# ESP32S3.net
KiCad netlist of a schematic drawn in Altium Designer
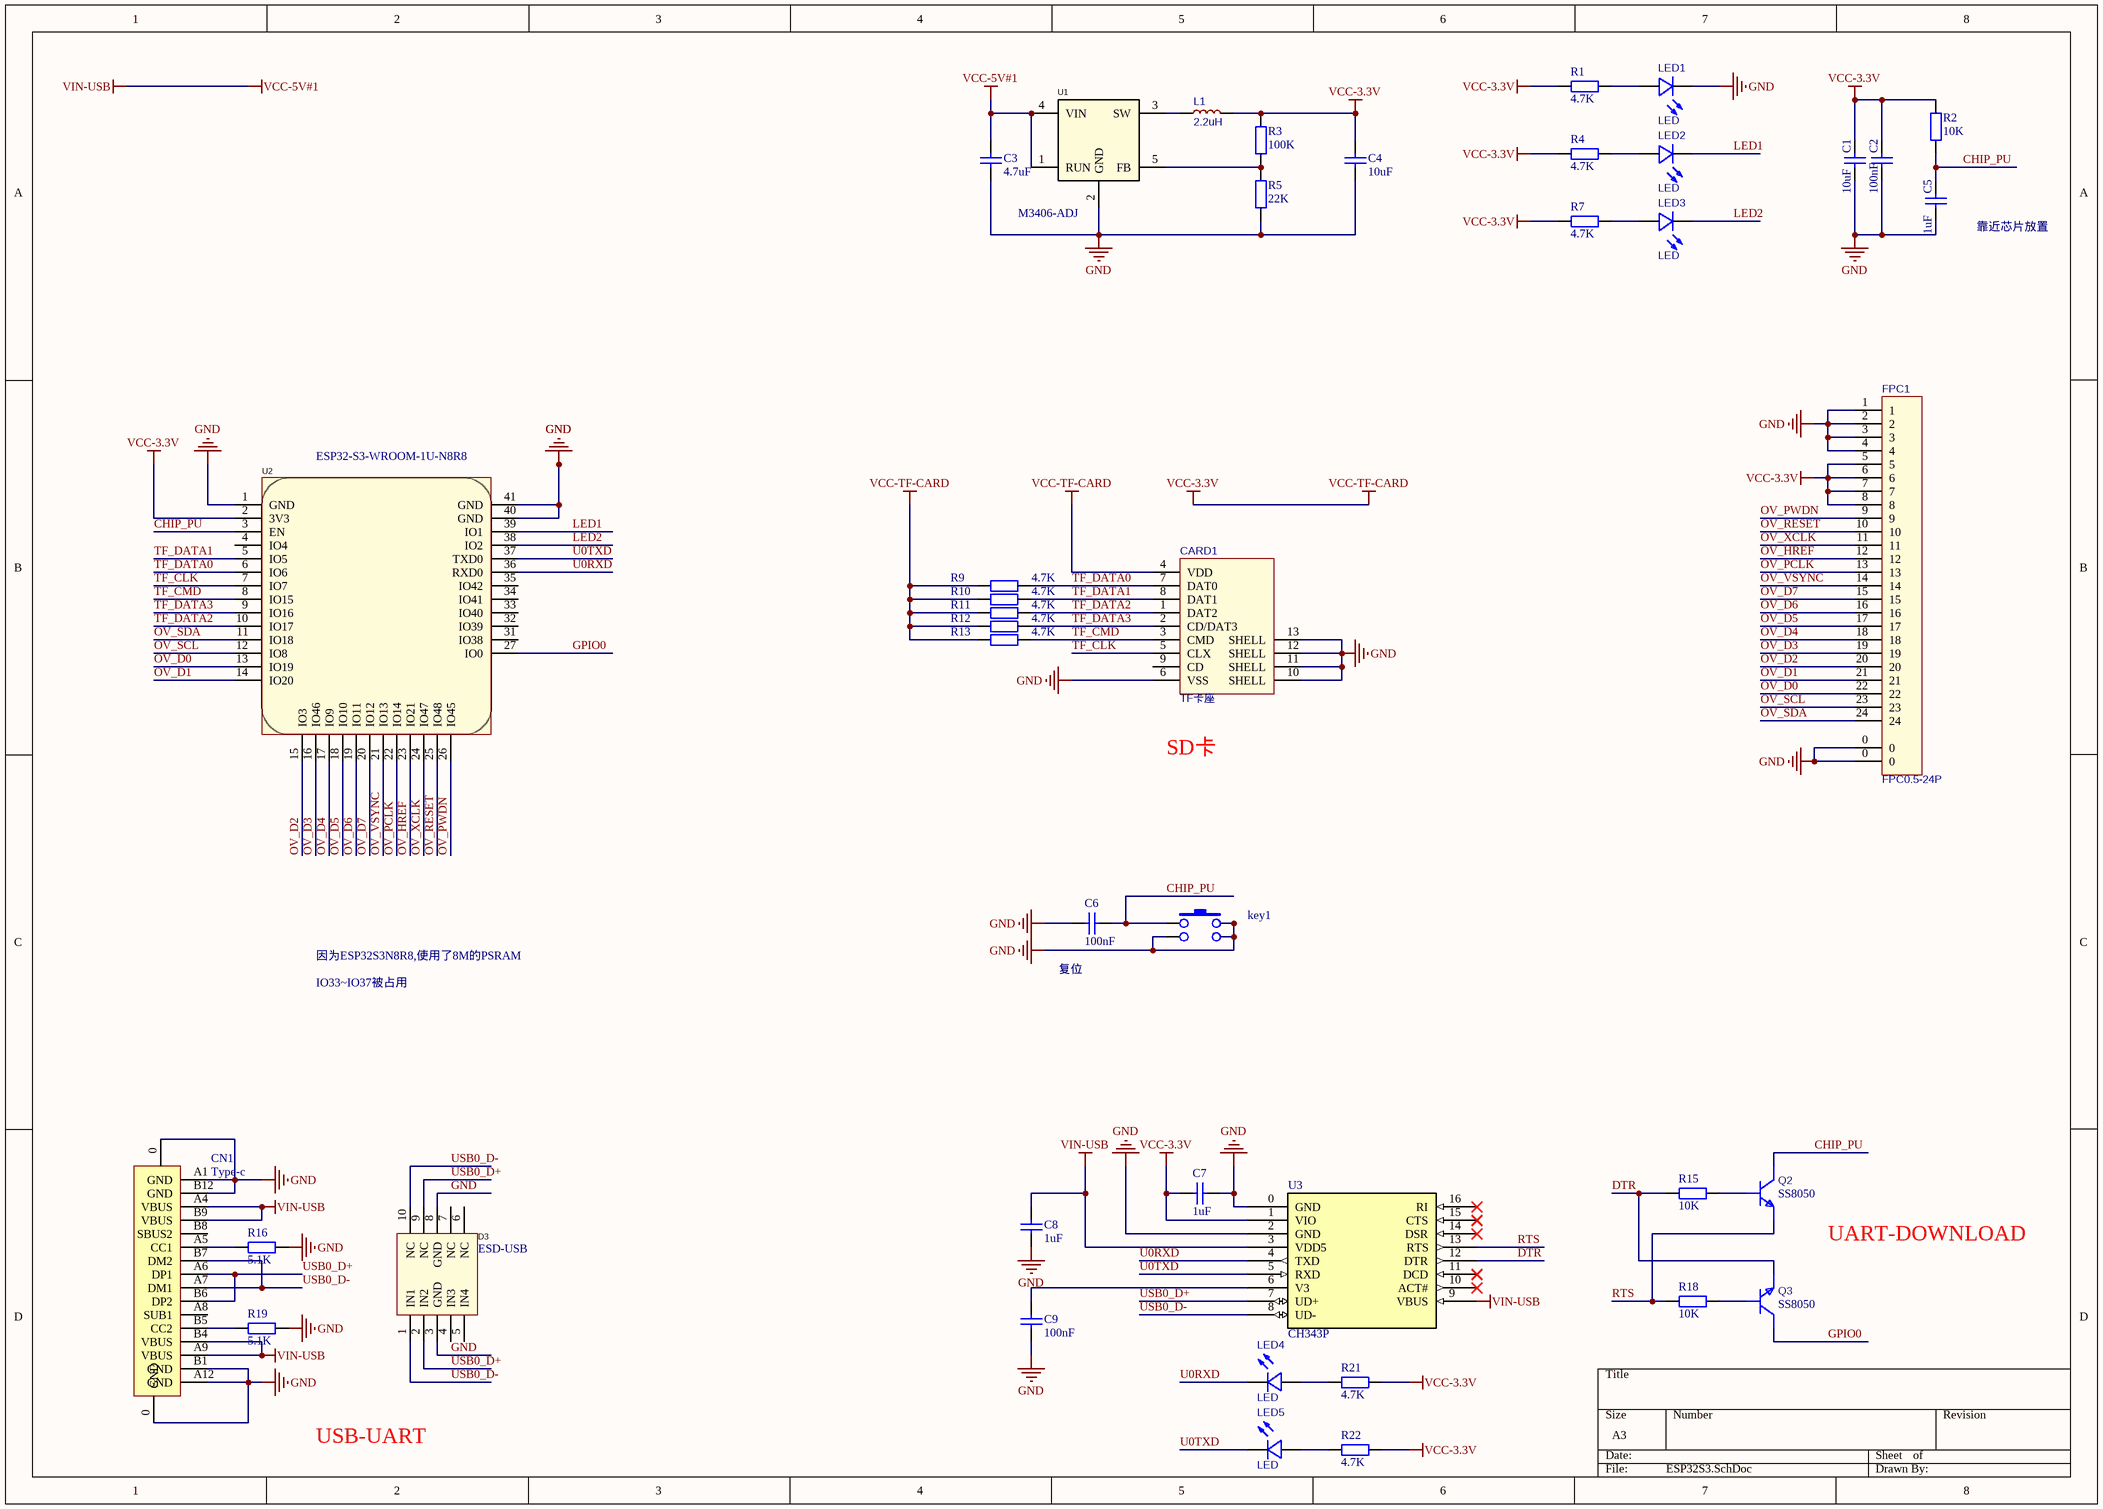
[diagram p0: ESP32S3.SchDoc]

(export (version "E")
  (design (tool "Eeschema 10.0.6"))
  (components
    (comp (ref "C1")
      (value "10uF")
      (footprint "0603-C")
      (description "贴片电容")
      (libsource (lib "封装库") (part "C"))
    )
    (comp (ref "C2")
      (value "100nF")
      (footprint "0603-C")
      (description "贴片电容")
      (libsource (lib "封装库") (part "C"))
    )
    (comp (ref "C3")
      (value "4.7uF")
      (footprint "0603-C")
      (description "贴片电容")
      (libsource (lib "封装库") (part "C"))
    )
    (comp (ref "C4")
      (value "10uF")
      (footprint "0603-C")
      (description "贴片电容")
      (libsource (lib "封装库") (part "C"))
    )
    (comp (ref "C5")
      (value "1uF")
      (footprint "0603-C")
      (description "贴片电容")
      (libsource (lib "封装库") (part "C"))
    )
    (comp (ref "C6")
      (value "100nF")
      (footprint "0603-C")
      (description "贴片电容")
      (libsource (lib "封装库") (part "C"))
    )
    (comp (ref "C7")
      (value "1uF")
      (footprint "0603-C")
      (description "贴片电容")
      (libsource (lib "封装库") (part "C"))
    )
    (comp (ref "C8")
      (value "1uF")
      (footprint "0603-C")
      (description "贴片电容")
      (libsource (lib "封装库") (part "C"))
    )
    (comp (ref "C9")
      (value "100nF")
      (footprint "0603-C")
      (description "贴片电容")
      (libsource (lib "封装库") (part "C"))
    )
    (comp (ref "CARD1")
      (value "TF卡座")
      (footprint "TF")
      (fields
        (field (name "BOM_SUPPLIER PART") "C283232")
        (field (name "BOM_MANUFACTURER PART") "THD2528-11SD-GF")
        (field (name "CONTRIBUTOR") "LCSC")
      )
      (libsource (lib "封装库") (part "TF卡座"))
    )
    (comp (ref "CN1")
      (value "Type-c")
      (footprint "Type-c 16pin")
      (description "U262-161N-4BVC11")
      (libsource (lib "封装") (part "Type-c"))
    )
    (comp (ref "D3")
      (value "ESD-USB")
      (footprint "SLP2510P8")
      (description "RClamp0524PATCT")
      (fields (field (name "MANUFACTURER") "SEMTECH"))
      (libsource (lib "封装库") (part "ESD-USB"))
    )
    (comp (ref "FPC1")
      (value "FPC0.5-24P")
      (footprint "FPC-SMD_P0.50-24P_XJ-FGS")
      (fields (field (name "BOM_SUPPLIER PART") "C132514") (field (name "CONTRIBUTOR") "LCSC"))
      (libsource (lib "封装库") (part "FPC0.5-24P"))
    )
    (comp (ref "key1") (value "KEY") (footprint "轻触开关侧按3*6*3.5") (libsource (lib "封装库") (part "轻触开关3*6*3.6")))
    (comp (ref "L1")
      (value "2.2uH")
      (footprint "电感 4.2X4.4")
      (description "L")
      (fields
        (field (name "BOM_MANUFACTURER PART") "UPZ2012D800-4R0TF")
        (field (name "BOM_SUPPLIER PART") "C145060")
        (field (name "CONTRIBUTOR") "LCSC")
      )
      (libsource (lib "封装库") (part "L"))
    )
    (comp (ref "LED1")
      (value "LED")
      (footprint "LED-0603")
      (fields
        (field (name "BOM_SUPPLIER PART") "C118334")
        (field (name "BOM_MANUFACTURER PART") "D-G060306G1-KS2")
        (field (name "CONTRIBUTOR") "LCSC")
      )
      (libsource (lib "封装库") (part "LED"))
    )
    (comp (ref "LED2")
      (value "LED")
      (footprint "LED-0603")
      (fields
        (field (name "BOM_SUPPLIER PART") "C118334")
        (field (name "BOM_MANUFACTURER PART") "D-G060306G1-KS2")
        (field (name "CONTRIBUTOR") "LCSC")
      )
      (libsource (lib "封装库") (part "LED"))
    )
    (comp (ref "LED3")
      (value "LED")
      (footprint "LED-0603")
      (fields
        (field (name "BOM_SUPPLIER PART") "C118334")
        (field (name "BOM_MANUFACTURER PART") "D-G060306G1-KS2")
        (field (name "CONTRIBUTOR") "LCSC")
      )
      (libsource (lib "封装库") (part "LED"))
    )
    (comp (ref "LED4")
      (value "LED")
      (footprint "LED-0603")
      (fields
        (field (name "BOM_SUPPLIER PART") "C118334")
        (field (name "BOM_MANUFACTURER PART") "D-G060306G1-KS2")
        (field (name "CONTRIBUTOR") "LCSC")
      )
      (libsource (lib "封装库") (part "LED"))
    )
    (comp (ref "LED5")
      (value "LED")
      (footprint "LED-0603")
      (fields
        (field (name "BOM_SUPPLIER PART") "C118334")
        (field (name "BOM_MANUFACTURER PART") "D-G060306G1-KS2")
        (field (name "CONTRIBUTOR") "LCSC")
      )
      (libsource (lib "封装库") (part "LED"))
    )
    (comp (ref "Q2") (value "SS8050") (footprint "SOT23-3M") (libsource (lib "封装库") (part "SS8050")))
    (comp (ref "Q3") (value "SS8050") (footprint "SOT23-3M") (libsource (lib "封装库") (part "SS8050")))
    (comp (ref "R1")
      (value "4.7K")
      (footprint "0603-R")
      (description "贴片电阻")
      (libsource (lib "封装库") (part "R"))
    )
    (comp (ref "R2")
      (value "10K")
      (footprint "0603-R")
      (description "贴片电阻")
      (libsource (lib "封装库") (part "R"))
    )
    (comp (ref "R3")
      (value "100K")
      (footprint "0603-R")
      (description "贴片电阻")
      (libsource (lib "封装库") (part "R"))
    )
    (comp (ref "R4")
      (value "4.7K")
      (footprint "0603-R")
      (description "贴片电阻")
      (libsource (lib "封装库") (part "R"))
    )
    (comp (ref "R5")
      (value "22K")
      (footprint "0603-R")
      (description "贴片电阻")
      (libsource (lib "封装库") (part "R"))
    )
    (comp (ref "R7")
      (value "4.7K")
      (footprint "0603-R")
      (description "贴片电阻")
      (libsource (lib "封装库") (part "R"))
    )
    (comp (ref "R9")
      (value "4.7K")
      (footprint "0603-R")
      (description "贴片电阻")
      (libsource (lib "封装库") (part "R"))
    )
    (comp (ref "R10")
      (value "4.7K")
      (footprint "0603-R")
      (description "贴片电阻")
      (libsource (lib "封装库") (part "R"))
    )
    (comp (ref "R11")
      (value "4.7K")
      (footprint "0603-R")
      (description "贴片电阻")
      (libsource (lib "封装库") (part "R"))
    )
    (comp (ref "R12")
      (value "4.7K")
      (footprint "0603-R")
      (description "贴片电阻")
      (libsource (lib "封装库") (part "R"))
    )
    (comp (ref "R13")
      (value "4.7K")
      (footprint "0603-R")
      (description "贴片电阻")
      (libsource (lib "封装库") (part "R"))
    )
    (comp (ref "R15")
      (value "10K")
      (footprint "0603-R")
      (description "贴片电阻")
      (libsource (lib "封装库") (part "R"))
    )
    (comp (ref "R16")
      (value "5.1K")
      (footprint "0603-R")
      (description "贴片电阻")
      (libsource (lib "封装库") (part "R"))
    )
    (comp (ref "R18")
      (value "10K")
      (footprint "0603-R")
      (description "贴片电阻")
      (libsource (lib "封装库") (part "R"))
    )
    (comp (ref "R19")
      (value "5.1K")
      (footprint "0603-R")
      (description "贴片电阻")
      (libsource (lib "封装库") (part "R"))
    )
    (comp (ref "R21")
      (value "4.7K")
      (footprint "0603-R")
      (description "贴片电阻")
      (libsource (lib "封装库") (part "R"))
    )
    (comp (ref "R22")
      (value "4.7K")
      (footprint "0603-R")
      (description "贴片电阻")
      (libsource (lib "封装库") (part "R"))
    )
    (comp (ref "U1")
      (value "M3406-ADJ")
      (footprint "M3406-ADJ")
      (fields (field (name "MANUFACTURER") "西安航天民芯"))
      (libsource (lib "封装库") (part "M3406-ADJ"))
    )
    (comp (ref "U2")
      (value "ESP32-S3-WROOM-1U-N8R8")
      (footprint "WIRELM-SMD_ESP32-S3-WROOM-1U")
      (fields
        (field (name "MANUFACTURER") "ESPRESSIF(乐鑫)")
        (field (name "MANUFACTURER PART") "ESP32-S3-WROOM-1U-N8")
      )
      (libsource (lib "封装库") (part "ESP32-S3-WROOM-1U-N8R8"))
    )
    (comp (ref "U3")
      (value "CH343P")
      (footprint "QFN16_3X3")
      (description "USB to high speed enhanced TTL Serial / UART")
      (libsource (lib "封装库") (part "CH343P"))
    )
  )
  (nets
    (net (code "1") (name "/CHIP_PU") (class "Default")
      (node (ref "C5") (pin "1") (pinfunction "1_1") (pintype "passive"))
      (node (ref "C6") (pin "1") (pinfunction "1_1") (pintype "passive"))
      (node (ref "Q2") (pin "3") (pinfunction "C_3") (pintype "passive"))
      (node (ref "R2") (pin "1") (pinfunction "1_1") (pintype "passive"))
      (node (ref "U2") (pin "3") (pinfunction "EN_3") (pintype "passive"))
      (node (ref "key1") (pin "1") (pinfunction "1_1") (pintype "passive"))
    )
    (net (code "2") (name "/DTR") (class "Default")
      (node (ref "Q3") (pin "2") (pinfunction "E_2") (pintype "passive"))
      (node (ref "R15") (pin "1") (pinfunction "1_1") (pintype "passive"))
      (node (ref "U3") (pin "12") (pinfunction "DTR_12") (pintype "output"))
    )
    (net (code "3") (name "/GPIO0") (class "Default")
      (node (ref "Q3") (pin "3") (pinfunction "C_3") (pintype "passive"))
      (node (ref "U2") (pin "27") (pinfunction "IO0_27") (pintype "passive"))
    )
    (net (code "4") (name "/LED1") (class "Default")
      (node (ref "LED2") (pin "1") (pinfunction "-_1") (pintype "passive"))
      (node (ref "U2") (pin "39") (pinfunction "IO1_39") (pintype "passive"))
    )
    (net (code "5") (name "/LED2") (class "Default")
      (node (ref "LED3") (pin "1") (pinfunction "-_1") (pintype "passive"))
      (node (ref "U2") (pin "38") (pinfunction "IO2_38") (pintype "passive"))
    )
    (net (code "6") (name "/OV_D0") (class "Default")
      (node (ref "FPC1") (pin "22") (pinfunction "22_22") (pintype "passive"))
      (node (ref "U2") (pin "13") (pinfunction "IO19_13") (pintype "passive"))
    )
    (net (code "7") (name "/OV_D1") (class "Default")
      (node (ref "FPC1") (pin "21") (pinfunction "21_21") (pintype "passive"))
      (node (ref "U2") (pin "14") (pinfunction "IO20_14") (pintype "passive"))
    )
    (net (code "8") (name "/OV_D2") (class "Default")
      (node (ref "FPC1") (pin "20") (pinfunction "20_20") (pintype "passive"))
      (node (ref "U2") (pin "15") (pinfunction "IO3_15") (pintype "passive"))
    )
    (net (code "9") (name "/OV_D3") (class "Default")
      (node (ref "FPC1") (pin "19") (pinfunction "19_19") (pintype "passive"))
      (node (ref "U2") (pin "16") (pinfunction "IO46_16") (pintype "passive"))
    )
    (net (code "10") (name "/OV_D4") (class "Default")
      (node (ref "FPC1") (pin "18") (pinfunction "18_18") (pintype "passive"))
      (node (ref "U2") (pin "17") (pinfunction "IO9_17") (pintype "passive"))
    )
    (net (code "11") (name "/OV_D5") (class "Default")
      (node (ref "FPC1") (pin "17") (pinfunction "17_17") (pintype "passive"))
      (node (ref "U2") (pin "18") (pinfunction "IO10_18") (pintype "passive"))
    )
    (net (code "12") (name "/OV_D6") (class "Default")
      (node (ref "FPC1") (pin "16") (pinfunction "16_16") (pintype "passive"))
      (node (ref "U2") (pin "19") (pinfunction "IO11_19") (pintype "passive"))
    )
    (net (code "13") (name "/OV_D7") (class "Default")
      (node (ref "FPC1") (pin "15") (pinfunction "15_15") (pintype "passive"))
      (node (ref "U2") (pin "20") (pinfunction "IO12_20") (pintype "passive"))
    )
    (net (code "14") (name "/OV_HREF") (class "Default")
      (node (ref "FPC1") (pin "12") (pinfunction "12_12") (pintype "passive"))
      (node (ref "U2") (pin "23") (pinfunction "IO21_23") (pintype "passive"))
    )
    (net (code "15") (name "/OV_PCLK") (class "Default")
      (node (ref "FPC1") (pin "13") (pinfunction "13_13") (pintype "passive"))
      (node (ref "U2") (pin "22") (pinfunction "IO14_22") (pintype "passive"))
    )
    (net (code "16") (name "/OV_PWDN") (class "Default")
      (node (ref "FPC1") (pin "9") (pinfunction "9_9") (pintype "passive"))
      (node (ref "U2") (pin "26") (pinfunction "IO45_26") (pintype "passive"))
    )
    (net (code "17") (name "/OV_RESET") (class "Default")
      (node (ref "FPC1") (pin "10") (pinfunction "10_10") (pintype "passive"))
      (node (ref "U2") (pin "25") (pinfunction "IO48_25") (pintype "passive"))
    )
    (net (code "18") (name "/OV_SCL") (class "Default")
      (node (ref "FPC1") (pin "23") (pinfunction "23_23") (pintype "passive"))
      (node (ref "U2") (pin "12") (pinfunction "IO8_12") (pintype "passive"))
    )
    (net (code "19") (name "/OV_SDA") (class "Default")
      (node (ref "FPC1") (pin "24") (pinfunction "24_24") (pintype "passive"))
      (node (ref "U2") (pin "11") (pinfunction "IO18_11") (pintype "passive"))
    )
    (net (code "20") (name "/OV_VSYNC") (class "Default")
      (node (ref "FPC1") (pin "14") (pinfunction "14_14") (pintype "passive"))
      (node (ref "U2") (pin "21") (pinfunction "IO13_21") (pintype "passive"))
    )
    (net (code "21") (name "/OV_XCLK") (class "Default")
      (node (ref "FPC1") (pin "11") (pinfunction "11_11") (pintype "passive"))
      (node (ref "U2") (pin "24") (pinfunction "IO47_24") (pintype "passive"))
    )
    (net (code "22") (name "/RTS") (class "Default")
      (node (ref "Q2") (pin "2") (pinfunction "E_2") (pintype "passive"))
      (node (ref "R18") (pin "1") (pinfunction "1_1") (pintype "passive"))
      (node (ref "U3") (pin "13") (pinfunction "RTS_13") (pintype "output"))
    )
    (net (code "23") (name "/TF_CLK") (class "Default")
      (node (ref "CARD1") (pin "5") (pinfunction "CLX_5") (pintype "passive"))
      (node (ref "U2") (pin "7") (pinfunction "IO7_7") (pintype "passive"))
    )
    (net (code "24") (name "/TF_CMD") (class "Default")
      (node (ref "CARD1") (pin "3") (pinfunction "CMD_3") (pintype "passive"))
      (node (ref "R13") (pin "2") (pinfunction "2_2") (pintype "passive"))
      (node (ref "U2") (pin "8") (pinfunction "IO15_8") (pintype "passive"))
    )
    (net (code "25") (name "/TF_DATA0") (class "Default")
      (node (ref "CARD1") (pin "7") (pinfunction "DAT0_7") (pintype "passive"))
      (node (ref "R9") (pin "2") (pinfunction "2_2") (pintype "passive"))
      (node (ref "U2") (pin "6") (pinfunction "IO6_6") (pintype "passive"))
    )
    (net (code "26") (name "/TF_DATA1") (class "Default")
      (node (ref "CARD1") (pin "8") (pinfunction "DAT1_8") (pintype "passive"))
      (node (ref "R10") (pin "2") (pinfunction "2_2") (pintype "passive"))
      (node (ref "U2") (pin "5") (pinfunction "IO5_5") (pintype "passive"))
    )
    (net (code "27") (name "/TF_DATA2") (class "Default")
      (node (ref "CARD1") (pin "1") (pinfunction "DAT2_1") (pintype "passive"))
      (node (ref "R11") (pin "2") (pinfunction "2_2") (pintype "passive"))
      (node (ref "U2") (pin "10") (pinfunction "IO17_10") (pintype "passive"))
    )
    (net (code "28") (name "/TF_DATA3") (class "Default")
      (node (ref "CARD1") (pin "2") (pinfunction "CD/DAT3_2") (pintype "passive"))
      (node (ref "R12") (pin "2") (pinfunction "2_2") (pintype "passive"))
      (node (ref "U2") (pin "9") (pinfunction "IO16_9") (pintype "passive"))
    )
    (net (code "29") (name "/U0RXD") (class "Default")
      (node (ref "LED4") (pin "1") (pinfunction "-_1") (pintype "passive"))
      (node (ref "U2") (pin "36") (pinfunction "RXD0_36") (pintype "passive"))
      (node (ref "U3") (pin "4") (pinfunction "TXD_4") (pintype "output"))
    )
    (net (code "30") (name "/U0TXD") (class "Default")
      (node (ref "LED5") (pin "1") (pinfunction "-_1") (pintype "passive"))
      (node (ref "U2") (pin "37") (pinfunction "TXD0_37") (pintype "passive"))
      (node (ref "U3") (pin "5") (pinfunction "RXD_5") (pintype "input"))
    )
    (net (code "31") (name "/USB0_D+") (class "Default")
      (node (ref "CN1") (pin "A6") (pinfunction "DP1_A6") (pintype "passive"))
      (node (ref "CN1") (pin "B6") (pinfunction "DP2_B6") (pintype "passive"))
      (node (ref "D3") (pin "2") (pinfunction "IN2_2") (pintype "passive"))
      (node (ref "D3") (pin "9") (pinfunction "NC_9") (pintype "passive"))
      (node (ref "U3") (pin "7") (pinfunction "UD+_7") (pintype "bidirectional"))
    )
    (net (code "32") (name "/USB0_D-") (class "Default")
      (node (ref "CN1") (pin "A7") (pinfunction "DM1_A7") (pintype "passive"))
      (node (ref "CN1") (pin "B7") (pinfunction "DM2_B7") (pintype "passive"))
      (node (ref "D3") (pin "1") (pinfunction "IN1_1") (pintype "passive"))
      (node (ref "D3") (pin "10") (pinfunction "NC_10") (pintype "passive"))
      (node (ref "U3") (pin "8") (pinfunction "UD-_8") (pintype "bidirectional"))
    )
    (net (code "33") (name "GND") (class "Default")
      (node (ref "C1") (pin "1") (pinfunction "1_1") (pintype "passive"))
      (node (ref "C2") (pin "2") (pinfunction "2_2") (pintype "passive"))
      (node (ref "C3") (pin "1") (pinfunction "1_1") (pintype "passive"))
      (node (ref "C4") (pin "1") (pinfunction "1_1") (pintype "passive"))
      (node (ref "C5") (pin "2") (pinfunction "2_2") (pintype "passive"))
      (node (ref "C6") (pin "2") (pinfunction "2_2") (pintype "passive"))
      (node (ref "C7") (pin "2") (pinfunction "2_2") (pintype "passive"))
      (node (ref "C8") (pin "2") (pinfunction "2_2") (pintype "passive"))
      (node (ref "C9") (pin "2") (pinfunction "2_2") (pintype "passive"))
      (node (ref "CARD1") (pin "10") (pinfunction "SHELL_10") (pintype "passive"))
      (node (ref "CARD1") (pin "11") (pinfunction "SHELL_11") (pintype "passive"))
      (node (ref "CARD1") (pin "12") (pinfunction "SHELL_12") (pintype "passive"))
      (node (ref "CARD1") (pin "13") (pinfunction "SHELL_13") (pintype "passive"))
      (node (ref "CARD1") (pin "6") (pinfunction "VSS_6") (pintype "passive"))
      (node (ref "CN1") (pin "0") (pinfunction "GND_0") (pintype "passive"))
      (node (ref "CN1") (pin "A1") (pinfunction "GND_A1") (pintype "passive"))
      (node (ref "CN1") (pin "A12") (pinfunction "GND_A12") (pintype "passive"))
      (node (ref "CN1") (pin "B1") (pinfunction "GND_B1") (pintype "passive"))
      (node (ref "CN1") (pin "B12") (pinfunction "GND_B12") (pintype "passive"))
      (node (ref "D3") (pin "3") (pinfunction "GND_3") (pintype "passive"))
      (node (ref "D3") (pin "8") (pinfunction "GND_8") (pintype "passive"))
      (node (ref "FPC1") (pin "0") (pinfunction "0_0") (pintype "passive"))
      (node (ref "FPC1") (pin "1") (pinfunction "1_1") (pintype "passive"))
      (node (ref "FPC1") (pin "2") (pinfunction "2_2") (pintype "passive"))
      (node (ref "FPC1") (pin "3") (pinfunction "3_3") (pintype "passive"))
      (node (ref "FPC1") (pin "4") (pinfunction "4_4") (pintype "passive"))
      (node (ref "LED1") (pin "1") (pinfunction "-_1") (pintype "passive"))
      (node (ref "R16") (pin "2") (pinfunction "2_2") (pintype "passive"))
      (node (ref "R19") (pin "2") (pinfunction "2_2") (pintype "passive"))
      (node (ref "R5") (pin "2") (pinfunction "2_2") (pintype "passive"))
      (node (ref "U1") (pin "2") (pinfunction "GND_2") (pintype "passive"))
      (node (ref "U2") (pin "1") (pinfunction "GND_1") (pintype "passive"))
      (node (ref "U2") (pin "40") (pinfunction "GND_40") (pintype "passive"))
      (node (ref "U2") (pin "41") (pinfunction "GND_41") (pintype "passive"))
      (node (ref "U3") (pin "0") (pinfunction "GND_0") (pintype "power_in"))
      (node (ref "U3") (pin "2") (pinfunction "GND_2") (pintype "power_in"))
      (node (ref "key1") (pin "2") (pinfunction "2_2") (pintype "passive"))
      (node (ref "key1") (pin "3") (pinfunction "3_3") (pintype "passive"))
      (node (ref "key1") (pin "4") (pinfunction "4_4") (pintype "passive"))
    )
    (net (code "34") (name "Net-(CN1-CC1)") (class "Default")
      (node (ref "CN1") (pin "A5") (pinfunction "CC1_A5") (pintype "passive"))
      (node (ref "R16") (pin "1") (pinfunction "1_1") (pintype "passive"))
    )
    (net (code "35") (name "Net-(CN1-CC2)") (class "Default")
      (node (ref "CN1") (pin "B5") (pinfunction "CC2_B5") (pintype "passive"))
      (node (ref "R19") (pin "1") (pinfunction "1_1") (pintype "passive"))
    )
    (net (code "36") (name "Net-(LED1-+)") (class "Default")
      (node (ref "LED1") (pin "2") (pinfunction "+_2") (pintype "passive"))
      (node (ref "R1") (pin "2") (pinfunction "2_2") (pintype "passive"))
    )
    (net (code "37") (name "Net-(LED2-+)") (class "Default")
      (node (ref "LED2") (pin "2") (pinfunction "+_2") (pintype "passive"))
      (node (ref "R4") (pin "2") (pinfunction "2_2") (pintype "passive"))
    )
    (net (code "38") (name "Net-(LED3-+)") (class "Default")
      (node (ref "LED3") (pin "2") (pinfunction "+_2") (pintype "passive"))
      (node (ref "R7") (pin "2") (pinfunction "2_2") (pintype "passive"))
    )
    (net (code "39") (name "Net-(LED4-+)") (class "Default")
      (node (ref "LED4") (pin "2") (pinfunction "+_2") (pintype "passive"))
      (node (ref "R21") (pin "2") (pinfunction "2_2") (pintype "passive"))
    )
    (net (code "40") (name "Net-(LED5-+)") (class "Default")
      (node (ref "LED5") (pin "2") (pinfunction "+_2") (pintype "passive"))
      (node (ref "R22") (pin "2") (pinfunction "2_2") (pintype "passive"))
    )
    (net (code "41") (name "Net-(Q2-B)") (class "Default")
      (node (ref "Q2") (pin "1") (pinfunction "B_1") (pintype "passive"))
      (node (ref "R15") (pin "2") (pinfunction "2_2") (pintype "passive"))
    )
    (net (code "42") (name "Net-(Q3-B)") (class "Default")
      (node (ref "Q3") (pin "1") (pinfunction "B_1") (pintype "passive"))
      (node (ref "R18") (pin "2") (pinfunction "2_2") (pintype "passive"))
    )
    (net (code "43") (name "Net-(U1-FB)") (class "Default")
      (node (ref "R3") (pin "1") (pinfunction "1_1") (pintype "passive"))
      (node (ref "R5") (pin "1") (pinfunction "1_1") (pintype "passive"))
      (node (ref "U1") (pin "5") (pinfunction "FB_5") (pintype "passive"))
    )
    (net (code "44") (name "Net-(U1-SW)") (class "Default")
      (node (ref "L1") (pin "1") (pinfunction "1_1") (pintype "passive"))
      (node (ref "U1") (pin "3") (pinfunction "SW_3") (pintype "passive"))
    )
    (net (code "45") (name "Net-(U3-V3)") (class "Default")
      (node (ref "C9") (pin "1") (pinfunction "1_1") (pintype "passive"))
      (node (ref "U3") (pin "6") (pinfunction "V3_6") (pintype "power_in"))
    )
    (net (code "46") (name "VCC-3.3V") (class "Default")
      (node (ref "C1") (pin "2") (pinfunction "2_2") (pintype "passive"))
      (node (ref "C2") (pin "1") (pinfunction "1_1") (pintype "passive"))
      (node (ref "C4") (pin "2") (pinfunction "2_2") (pintype "passive"))
      (node (ref "C7") (pin "1") (pinfunction "1_1") (pintype "passive"))
      (node (ref "CARD1") (pin "4") (pinfunction "VDD_4") (pintype "passive"))
      (node (ref "FPC1") (pin "5") (pinfunction "5_5") (pintype "passive"))
      (node (ref "FPC1") (pin "6") (pinfunction "6_6") (pintype "passive"))
      (node (ref "FPC1") (pin "7") (pinfunction "7_7") (pintype "passive"))
      (node (ref "FPC1") (pin "8") (pinfunction "8_8") (pintype "passive"))
      (node (ref "L1") (pin "2") (pinfunction "2_2") (pintype "passive"))
      (node (ref "R1") (pin "1") (pinfunction "1_1") (pintype "passive"))
      (node (ref "R10") (pin "1") (pinfunction "1_1") (pintype "passive"))
      (node (ref "R11") (pin "1") (pinfunction "1_1") (pintype "passive"))
      (node (ref "R12") (pin "1") (pinfunction "1_1") (pintype "passive"))
      (node (ref "R13") (pin "1") (pinfunction "1_1") (pintype "passive"))
      (node (ref "R2") (pin "2") (pinfunction "2_2") (pintype "passive"))
      (node (ref "R21") (pin "1") (pinfunction "1_1") (pintype "passive"))
      (node (ref "R22") (pin "1") (pinfunction "1_1") (pintype "passive"))
      (node (ref "R3") (pin "2") (pinfunction "2_2") (pintype "passive"))
      (node (ref "R4") (pin "1") (pinfunction "1_1") (pintype "passive"))
      (node (ref "R7") (pin "1") (pinfunction "1_1") (pintype "passive"))
      (node (ref "R9") (pin "1") (pinfunction "1_1") (pintype "passive"))
      (node (ref "U2") (pin "2") (pinfunction "3V3_2") (pintype "passive"))
      (node (ref "U3") (pin "1") (pinfunction "VIO_1") (pintype "power_in"))
    )
    (net (code "47") (name "VCC-5V#1") (class "Default")
      (node (ref "C3") (pin "2") (pinfunction "2_2") (pintype "passive"))
      (node (ref "C8") (pin "1") (pinfunction "1_1") (pintype "passive"))
      (node (ref "CN1") (pin "A4") (pinfunction "VBUS_A4") (pintype "passive"))
      (node (ref "CN1") (pin "A9") (pinfunction "VBUS_A9") (pintype "passive"))
      (node (ref "CN1") (pin "B4") (pinfunction "VBUS_B4") (pintype "passive"))
      (node (ref "CN1") (pin "B9") (pinfunction "VBUS_B9") (pintype "passive"))
      (node (ref "U1") (pin "1") (pinfunction "RUN_1") (pintype "passive"))
      (node (ref "U1") (pin "4") (pinfunction "VIN_4") (pintype "passive"))
      (node (ref "U3") (pin "3") (pinfunction "VDD5_3") (pintype "power_in"))
      (node (ref "U3") (pin "9") (pinfunction "VBUS_9") (pintype "input"))
    )
    (net (code "48") (name "unconnected-(CARD1-CD-Pad9)") (class "Default")
      (node (ref "CARD1") (pin "9") (pinfunction "CD_9") (pintype "passive"))
    )
    (net (code "49") (name "unconnected-(CN1-SBUS2-PadB8)") (class "Default")
      (node (ref "CN1") (pin "B8") (pinfunction "SBUS2_B8") (pintype "passive"))
    )
    (net (code "50") (name "unconnected-(CN1-SUB1-PadA8)") (class "Default")
      (node (ref "CN1") (pin "A8") (pinfunction "SUB1_A8") (pintype "passive"))
    )
    (net (code "51") (name "unconnected-(D3-IN3-Pad4)") (class "Default")
      (node (ref "D3") (pin "4") (pinfunction "IN3_4") (pintype "passive"))
    )
    (net (code "52") (name "unconnected-(D3-IN4-Pad5)") (class "Default")
      (node (ref "D3") (pin "5") (pinfunction "IN4_5") (pintype "passive"))
    )
    (net (code "53") (name "unconnected-(D3-NC-Pad6)") (class "Default")
      (node (ref "D3") (pin "6") (pinfunction "NC_6") (pintype "passive"))
    )
    (net (code "54") (name "unconnected-(D3-NC-Pad7)") (class "Default")
      (node (ref "D3") (pin "7") (pinfunction "NC_7") (pintype "passive"))
    )
    (net (code "55") (name "unconnected-(U2-IO4-Pad4)") (class "Default")
      (node (ref "U2") (pin "4") (pinfunction "IO4_4") (pintype "passive"))
    )
    (net (code "56") (name "unconnected-(U2-IO38-Pad31)") (class "Default")
      (node (ref "U2") (pin "31") (pinfunction "IO38_31") (pintype "passive"))
    )
    (net (code "57") (name "unconnected-(U2-IO39-Pad32)") (class "Default")
      (node (ref "U2") (pin "32") (pinfunction "IO39_32") (pintype "passive"))
    )
    (net (code "58") (name "unconnected-(U2-IO40-Pad33)") (class "Default")
      (node (ref "U2") (pin "33") (pinfunction "IO40_33") (pintype "passive"))
    )
    (net (code "59") (name "unconnected-(U2-IO41-Pad34)") (class "Default")
      (node (ref "U2") (pin "34") (pinfunction "IO41_34") (pintype "passive"))
    )
    (net (code "60") (name "unconnected-(U2-IO42-Pad35)") (class "Default")
      (node (ref "U2") (pin "35") (pinfunction "IO42_35") (pintype "passive"))
    )
    (net (code "61") (name "unconnected-(U3-ACT#-Pad10)") (class "Default")
      (node (ref "U3") (pin "10") (pinfunction "ACT#_10") (pintype "output+no_connect"))
    )
    (net (code "62") (name "unconnected-(U3-CTS-Pad15)") (class "Default")
      (node (ref "U3") (pin "15") (pinfunction "CTS_15") (pintype "input+no_connect"))
    )
    (net (code "63") (name "unconnected-(U3-DCD-Pad11)") (class "Default")
      (node (ref "U3") (pin "11") (pinfunction "DCD_11") (pintype "input+no_connect"))
    )
    (net (code "64") (name "unconnected-(U3-DSR-Pad14)") (class "Default")
      (node (ref "U3") (pin "14") (pinfunction "DSR_14") (pintype "input+no_connect"))
    )
    (net (code "65") (name "unconnected-(U3-RI-Pad16)") (class "Default")
      (node (ref "U3") (pin "16") (pinfunction "RI_16") (pintype "input+no_connect"))
    )
  )
)
